# rotary_encoder_5.net
KiCad netlist of a schematic drawn in EAGLE
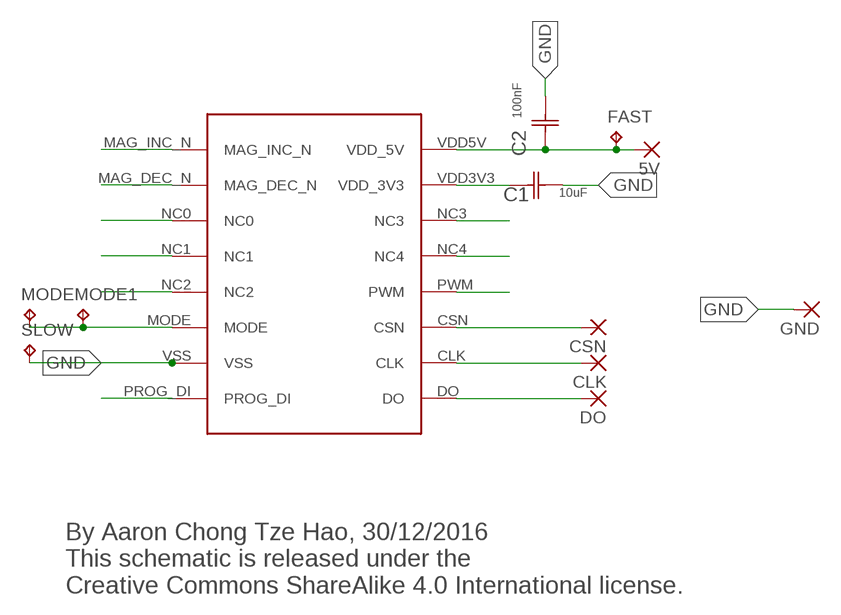
[diagram p0: schematic, sheet 1]

(export (version "E")
  (design (tool "Eeschema 10.0.6"))
  (components
    (comp (ref "5V")
      (value "1,6/0,8")
      (footprint "eagle-import:1,6_0,8")
      (libsource (lib "eagle-import") (part "1,6/0,8"))
    )
    (comp (ref "C1")
      (value "10uF")
      (footprint "eagle-import:CAP_0805_100NF")
      (fields (field (name "MPN") "0805F106Z100CT") (field (name "TOLERANCE") "-20/+80%"))
      (libsource (lib "eagle-import") (part "CAP_0805_10UF"))
    )
    (comp (ref "C2")
      (value "100nF")
      (footprint "eagle-import:CAP_0805_100NF")
      (fields (field (name "MPN") "U0805F104ZCT") (field (name "TOLERANCE") "-20/+80%"))
      (libsource (lib "eagle-import") (part "CAP_0805_100NF"))
    )
    (comp (ref "CLK")
      (value "1,6/0,8")
      (footprint "eagle-import:1,6_0,8")
      (libsource (lib "eagle-import") (part "1,6/0,8"))
    )
    (comp (ref "CSN")
      (value "1,6/0,8")
      (footprint "eagle-import:1,6_0,8")
      (libsource (lib "eagle-import") (part "1,6/0,8"))
    )
    (comp (ref "DO")
      (value "1,6/0,8")
      (footprint "eagle-import:1,6_0,8")
      (libsource (lib "eagle-import") (part "1,6/0,8"))
    )
    (comp (ref "FAST")
      (value "TPTP10SQ")
      (footprint "eagle-import:TP10SQ")
      (libsource (lib "eagle-import") (part "TPTP10SQ"))
    )
    (comp (ref "GND")
      (value "1,6/0,8")
      (footprint "eagle-import:1,6_0,8")
      (libsource (lib "eagle-import") (part "1,6/0,8"))
    )
    (comp (ref "MODE")
      (value "TPTP10SQ")
      (footprint "eagle-import:TP10SQ")
      (libsource (lib "eagle-import") (part "TPTP10SQ"))
    )
    (comp (ref "MODE1")
      (value "TPTP10SQ")
      (footprint "eagle-import:TP10SQ")
      (libsource (lib "eagle-import") (part "TPTP10SQ"))
    )
    (comp (ref "SLOW")
      (value "TPTP10SQ")
      (footprint "eagle-import:TP10SQ")
      (libsource (lib "eagle-import") (part "TPTP10SQ"))
    )
    (comp (ref "U$1")
      (value "AS5045_ROTARY_ENCODER")
      (footprint "eagle-import:AS5045_ROTARY_ENCODER")
      (libsource (lib "eagle-import") (part "AS5045_ROTARY_ENCODER"))
    )
  )
  (nets
    (net (code "1") (name "GND") (class "Default")
      (node (ref "C1") (pin "2") (pinfunction "C2_2") (pintype "passive"))
      (node (ref "C2") (pin "2") (pinfunction "C2_2") (pintype "passive"))
      (node (ref "GND") (pin "1") (pinfunction "P_1") (pintype "passive"))
      (node (ref "SLOW") (pin "TP") (pinfunction "TP_TP") (pintype "input"))
      (node (ref "U$1") (pin "VSS") (pinfunction "VSS_VSS") (pintype "bidirectional"))
    )
    (net (code "2") (name "Net-(5V-P)") (class "Default")
      (node (ref "5V") (pin "1") (pinfunction "P_1") (pintype "passive"))
      (node (ref "C2") (pin "1") (pinfunction "C1_1") (pintype "passive"))
      (node (ref "FAST") (pin "TP") (pinfunction "TP_TP") (pintype "input"))
      (node (ref "U$1") (pin "VDD5V") (pinfunction "VDD_5V_VDD5V") (pintype "bidirectional"))
    )
    (net (code "3") (name "Net-(C1-C1)") (class "Default")
      (node (ref "C1") (pin "1") (pinfunction "C1_1") (pintype "passive"))
      (node (ref "U$1") (pin "VDD3V3") (pinfunction "VDD_3V3_VDD3V3") (pintype "bidirectional"))
    )
    (net (code "4") (name "Net-(CLK-P)") (class "Default")
      (node (ref "CLK") (pin "1") (pinfunction "P_1") (pintype "passive"))
      (node (ref "U$1") (pin "CLK") (pinfunction "CLK_CLK") (pintype "bidirectional"))
    )
    (net (code "5") (name "Net-(CSN-P)") (class "Default")
      (node (ref "CSN") (pin "1") (pinfunction "P_1") (pintype "passive"))
      (node (ref "U$1") (pin "CSN") (pinfunction "CSN_CSN") (pintype "bidirectional"))
    )
    (net (code "6") (name "Net-(DO-P)") (class "Default")
      (node (ref "DO") (pin "1") (pinfunction "P_1") (pintype "passive"))
      (node (ref "U$1") (pin "DO") (pinfunction "DO_DO") (pintype "bidirectional"))
    )
    (net (code "7") (name "Net-(MODE-PadTP)") (class "Default")
      (node (ref "MODE") (pin "TP") (pinfunction "TP_TP") (pintype "input"))
      (node (ref "MODE1") (pin "TP") (pinfunction "TP_TP") (pintype "input"))
      (node (ref "U$1") (pin "MODE") (pinfunction "MODE_MODE") (pintype "bidirectional"))
    )
    (net (code "8") (name "unconnected-(U$1-PadMAG_DEC_N)") (class "Default")
      (node (ref "U$1") (pin "MAG_DEC_N") (pinfunction "MAG_DEC_N_MAG_DEC_N") (pintype "bidirectional"))
    )
    (net (code "9") (name "unconnected-(U$1-PadMAG_INC_N)") (class "Default")
      (node (ref "U$1") (pin "MAG_INC_N") (pinfunction "MAG_INC_N_MAG_INC_N") (pintype "bidirectional"))
    )
    (net (code "10") (name "unconnected-(U$1-PadNC0)") (class "Default")
      (node (ref "U$1") (pin "NC0") (pinfunction "NC0_NC0") (pintype "bidirectional"))
    )
    (net (code "11") (name "unconnected-(U$1-PadNC1)") (class "Default")
      (node (ref "U$1") (pin "NC1") (pinfunction "NC1_NC1") (pintype "bidirectional"))
    )
    (net (code "12") (name "unconnected-(U$1-PadNC2)") (class "Default")
      (node (ref "U$1") (pin "NC2") (pinfunction "NC2_NC2") (pintype "bidirectional"))
    )
    (net (code "13") (name "unconnected-(U$1-PadNC3)") (class "Default")
      (node (ref "U$1") (pin "NC3") (pinfunction "NC3_NC3") (pintype "bidirectional"))
    )
    (net (code "14") (name "unconnected-(U$1-PadNC4)") (class "Default")
      (node (ref "U$1") (pin "NC4") (pinfunction "NC4_NC4") (pintype "bidirectional"))
    )
    (net (code "15") (name "unconnected-(U$1-PadPROG_DI)") (class "Default")
      (node (ref "U$1") (pin "PROG_DI") (pinfunction "PROG_DI_PROG_DI") (pintype "bidirectional"))
    )
    (net (code "16") (name "unconnected-(U$1-PadPWM)") (class "Default")
      (node (ref "U$1") (pin "PWM") (pinfunction "PWM_PWM") (pintype "bidirectional"))
    )
  )
)
